# sdr_boosterpack.net
KiCad netlist of a schematic drawn in EAGLE
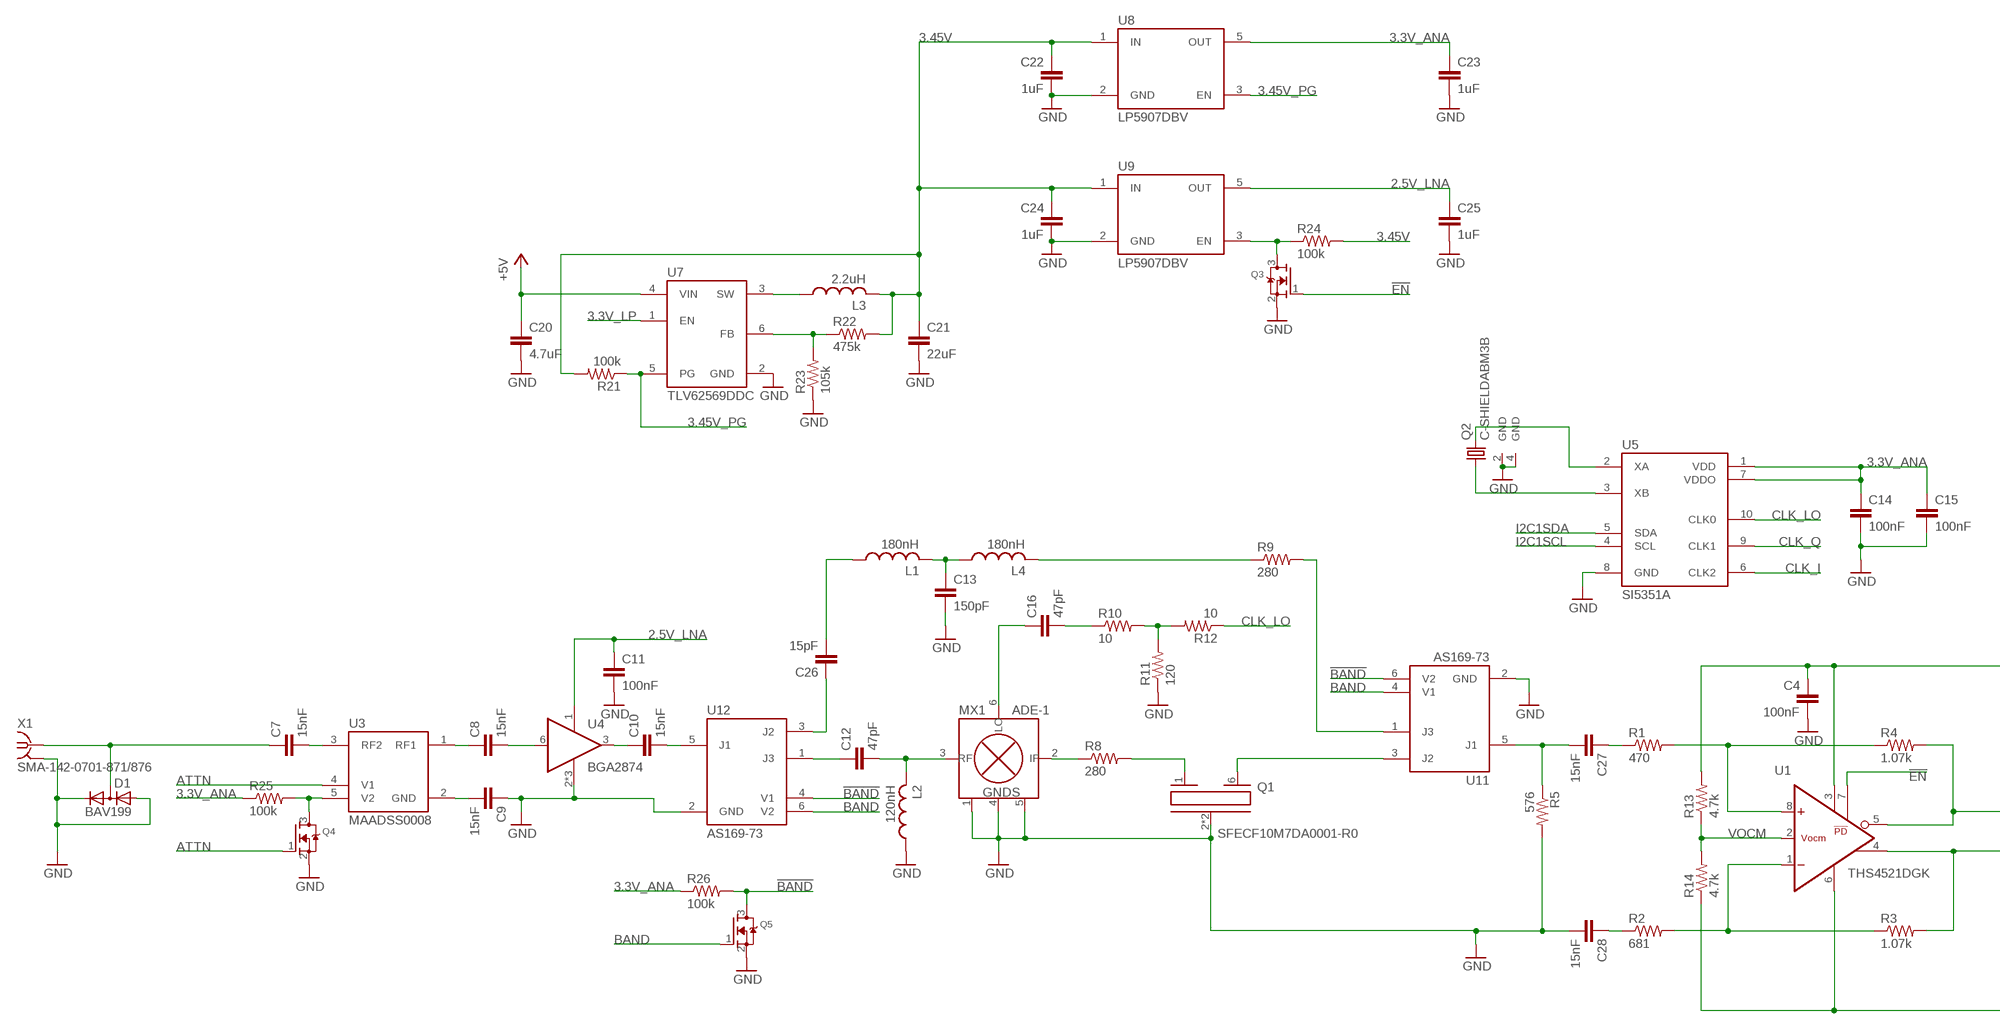
[diagram p0: schematic, sheet 1, part 1 of 2]
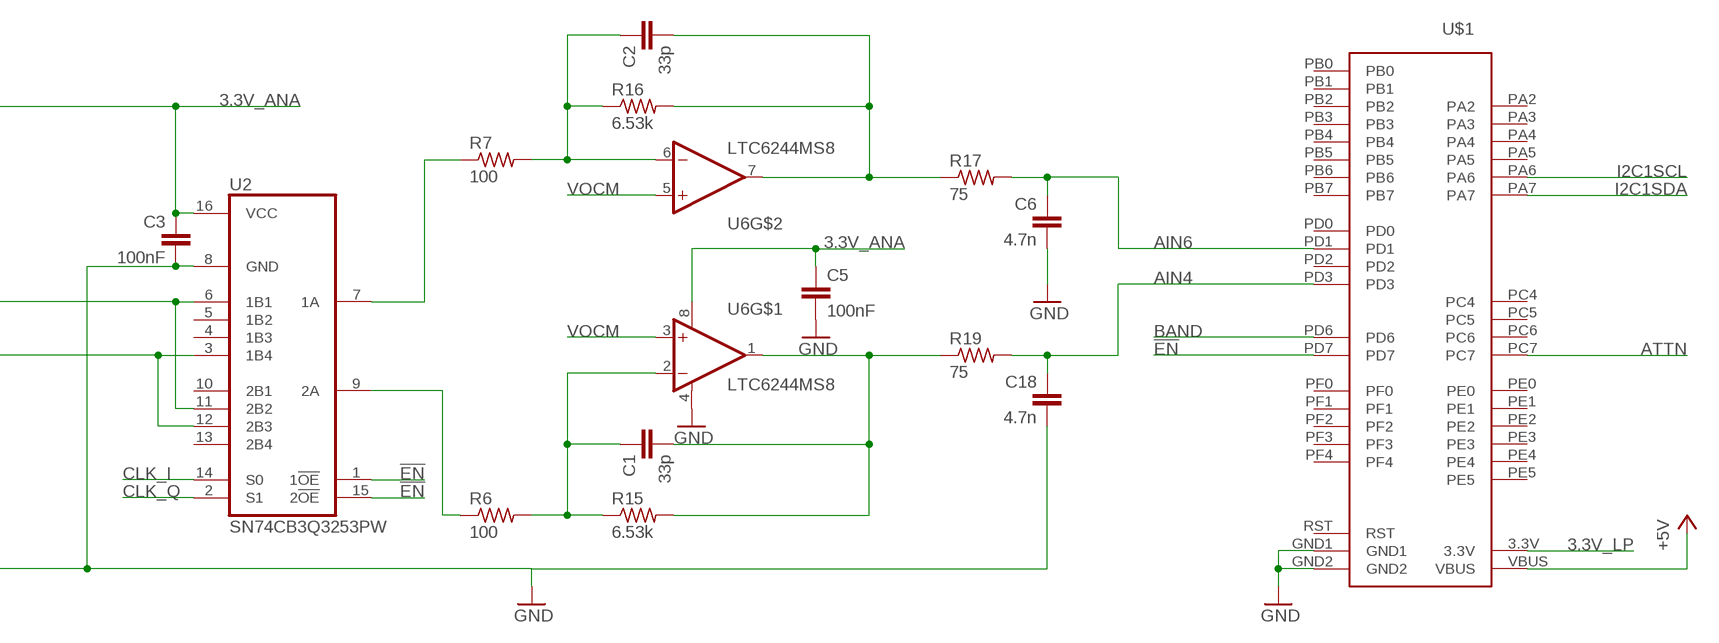
[diagram p1: schematic, sheet 1, part 2 of 2]

(export (version "E")
  (design (tool "Eeschema 10.0.6"))
  (components
    (comp (ref "C1")
      (value "33p")
      (footprint "eagle-import:C0603")
      (libsource (lib "eagle-import") (part "C-EUC0603"))
    )
    (comp (ref "C2")
      (value "33p")
      (footprint "eagle-import:C0603")
      (libsource (lib "eagle-import") (part "C-EUC0603"))
    )
    (comp (ref "C3")
      (value "100nF")
      (footprint "eagle-import:C0603")
      (libsource (lib "eagle-import") (part "C-EUC0603"))
    )
    (comp (ref "C4")
      (value "100nF")
      (footprint "eagle-import:C0603")
      (libsource (lib "eagle-import") (part "C-EUC0603"))
    )
    (comp (ref "C5")
      (value "100nF")
      (footprint "eagle-import:C0603")
      (libsource (lib "eagle-import") (part "C-EUC0603"))
    )
    (comp (ref "C6")
      (value "4.7n")
      (footprint "eagle-import:C0603")
      (libsource (lib "eagle-import") (part "C-EUC0603"))
    )
    (comp (ref "C7")
      (value "15nF")
      (footprint "eagle-import:C0603")
      (libsource (lib "eagle-import") (part "C-EUC0603"))
    )
    (comp (ref "C8")
      (value "15nF")
      (footprint "eagle-import:C0603")
      (libsource (lib "eagle-import") (part "C-EUC0603"))
    )
    (comp (ref "C9")
      (value "15nF")
      (footprint "eagle-import:C0603")
      (libsource (lib "eagle-import") (part "C-EUC0603"))
    )
    (comp (ref "C10")
      (value "15nF")
      (footprint "eagle-import:C0603")
      (libsource (lib "eagle-import") (part "C-EUC0603"))
    )
    (comp (ref "C11")
      (value "100nF")
      (footprint "eagle-import:C0603")
      (libsource (lib "eagle-import") (part "C-EUC0603"))
    )
    (comp (ref "C12")
      (value "47pF")
      (footprint "eagle-import:C0603")
      (libsource (lib "eagle-import") (part "C-EUC0603"))
    )
    (comp (ref "C13")
      (value "150pF")
      (footprint "eagle-import:C0603")
      (libsource (lib "eagle-import") (part "C-EUC0603"))
    )
    (comp (ref "C14")
      (value "100nF")
      (footprint "eagle-import:C0603")
      (libsource (lib "eagle-import") (part "C-EUC0603"))
    )
    (comp (ref "C15")
      (value "100nF")
      (footprint "eagle-import:C0603")
      (libsource (lib "eagle-import") (part "C-EUC0603"))
    )
    (comp (ref "C16")
      (value "47pF")
      (footprint "eagle-import:C0603")
      (libsource (lib "eagle-import") (part "C-EUC0603"))
    )
    (comp (ref "C18")
      (value "4.7n")
      (footprint "eagle-import:C0603")
      (libsource (lib "eagle-import") (part "C-EUC0603"))
    )
    (comp (ref "C20")
      (value "4.7uF")
      (footprint "eagle-import:C0805")
      (libsource (lib "eagle-import") (part "C-EUC0805"))
    )
    (comp (ref "C21")
      (value "22uF")
      (footprint "eagle-import:C0805")
      (libsource (lib "eagle-import") (part "C-EUC0805"))
    )
    (comp (ref "C22")
      (value "1uF")
      (footprint "eagle-import:C0805")
      (libsource (lib "eagle-import") (part "C-EUC0805"))
    )
    (comp (ref "C23")
      (value "1uF")
      (footprint "eagle-import:C0805")
      (libsource (lib "eagle-import") (part "C-EUC0805"))
    )
    (comp (ref "C24")
      (value "1uF")
      (footprint "eagle-import:C0805")
      (libsource (lib "eagle-import") (part "C-EUC0805"))
    )
    (comp (ref "C25")
      (value "1uF")
      (footprint "eagle-import:C0805")
      (libsource (lib "eagle-import") (part "C-EUC0805"))
    )
    (comp (ref "C26")
      (value "15pF")
      (footprint "eagle-import:C0603")
      (libsource (lib "eagle-import") (part "C-EUC0603"))
    )
    (comp (ref "C27")
      (value "15nF")
      (footprint "eagle-import:C0603")
      (libsource (lib "eagle-import") (part "C-EUC0603"))
    )
    (comp (ref "C28")
      (value "15nF")
      (footprint "eagle-import:C0603")
      (libsource (lib "eagle-import") (part "C-EUC0603"))
    )
    (comp (ref "D1")
      (value "BAV199")
      (footprint "eagle-import:SOT23")
      (libsource (lib "eagle-import") (part "BAV199"))
    )
    (comp (ref "L1")
      (value "180nH")
      (footprint "eagle-import:C0603")
      (libsource (lib "eagle-import") (part "L-US0603CS"))
    )
    (comp (ref "L2")
      (value "120nH")
      (footprint "eagle-import:C0603")
      (libsource (lib "eagle-import") (part "L-US0603CS"))
    )
    (comp (ref "L3")
      (value "2.2uH")
      (footprint "eagle-import:XAL4040")
      (libsource (lib "eagle-import") (part "L-USXAL4040"))
    )
    (comp (ref "L4")
      (value "180nH")
      (footprint "eagle-import:C0603")
      (libsource (lib "eagle-import") (part "L-US0603CS"))
    )
    (comp (ref "MX1")
      (value "ADE-1")
      (footprint "eagle-import:CD636")
      (libsource (lib "eagle-import") (part "ADE-1"))
    )
    (comp (ref "Q1")
      (value "SFECF10M7DA0001-R0")
      (footprint "eagle-import:SFECF")
      (libsource (lib "eagle-import") (part "SFECF"))
    )
    (comp (ref "Q2")
      (value "C-SHIELDABM3B")
      (footprint "eagle-import:ABM3B")
      (libsource (lib "eagle-import") (part "C-SHIELDABM3B"))
    )
    (comp (ref "Q3")
      (value "MOSFET-NREFLOW")
      (footprint "eagle-import:SOT23")
      (libsource (lib "eagle-import") (part "MOSFET-NREFLOW"))
    )
    (comp (ref "Q4")
      (value "MOSFET-NREFLOW")
      (footprint "eagle-import:SOT23")
      (libsource (lib "eagle-import") (part "MOSFET-NREFLOW"))
    )
    (comp (ref "Q5")
      (value "MOSFET-NREFLOW")
      (footprint "eagle-import:SOT23")
      (libsource (lib "eagle-import") (part "MOSFET-NREFLOW"))
    )
    (comp (ref "R1")
      (value "470")
      (footprint "eagle-import:R0603")
      (libsource (lib "eagle-import") (part "R-US_R0603"))
    )
    (comp (ref "R2")
      (value "681")
      (footprint "eagle-import:R0603")
      (libsource (lib "eagle-import") (part "R-US_R0603"))
    )
    (comp (ref "R3")
      (value "1.07k")
      (footprint "eagle-import:R0603")
      (libsource (lib "eagle-import") (part "R-US_R0603"))
    )
    (comp (ref "R4")
      (value "1.07k")
      (footprint "eagle-import:R0603")
      (libsource (lib "eagle-import") (part "R-US_R0603"))
    )
    (comp (ref "R5")
      (value "576")
      (footprint "eagle-import:R0603")
      (libsource (lib "eagle-import") (part "R-US_R0603"))
    )
    (comp (ref "R6")
      (value "100")
      (footprint "eagle-import:R0603")
      (libsource (lib "eagle-import") (part "R-US_R0603"))
    )
    (comp (ref "R7")
      (value "100")
      (footprint "eagle-import:R0603")
      (libsource (lib "eagle-import") (part "R-US_R0603"))
    )
    (comp (ref "R8")
      (value "280")
      (footprint "eagle-import:R0603")
      (libsource (lib "eagle-import") (part "R-US_R0603"))
    )
    (comp (ref "R9")
      (value "280")
      (footprint "eagle-import:R0603")
      (libsource (lib "eagle-import") (part "R-US_R0603"))
    )
    (comp (ref "R10")
      (value "10")
      (footprint "eagle-import:R0603")
      (libsource (lib "eagle-import") (part "R-US_R0603"))
    )
    (comp (ref "R11")
      (value "120")
      (footprint "eagle-import:R0603")
      (libsource (lib "eagle-import") (part "R-US_R0603"))
    )
    (comp (ref "R12")
      (value "10")
      (footprint "eagle-import:R0603")
      (libsource (lib "eagle-import") (part "R-US_R0603"))
    )
    (comp (ref "R13")
      (value "4.7k")
      (footprint "eagle-import:R0603")
      (libsource (lib "eagle-import") (part "R-US_R0603"))
    )
    (comp (ref "R14")
      (value "4.7k")
      (footprint "eagle-import:R0603")
      (libsource (lib "eagle-import") (part "R-US_R0603"))
    )
    (comp (ref "R15")
      (value "6.53k")
      (footprint "eagle-import:R0603")
      (libsource (lib "eagle-import") (part "R-US_R0603"))
    )
    (comp (ref "R16")
      (value "6.53k")
      (footprint "eagle-import:R0603")
      (libsource (lib "eagle-import") (part "R-US_R0603"))
    )
    (comp (ref "R17")
      (value "75")
      (footprint "eagle-import:R0603")
      (libsource (lib "eagle-import") (part "R-US_R0603"))
    )
    (comp (ref "R19")
      (value "75")
      (footprint "eagle-import:R0603")
      (libsource (lib "eagle-import") (part "R-US_R0603"))
    )
    (comp (ref "R21")
      (value "100k")
      (footprint "eagle-import:R0603")
      (libsource (lib "eagle-import") (part "R-US_R0603"))
    )
    (comp (ref "R22")
      (value "475k")
      (footprint "eagle-import:R0603")
      (libsource (lib "eagle-import") (part "R-US_R0603"))
    )
    (comp (ref "R23")
      (value "105k")
      (footprint "eagle-import:R0603")
      (libsource (lib "eagle-import") (part "R-US_R0603"))
    )
    (comp (ref "R24")
      (value "100k")
      (footprint "eagle-import:R0603")
      (libsource (lib "eagle-import") (part "R-US_R0603"))
    )
    (comp (ref "R25")
      (value "100k")
      (footprint "eagle-import:R0603")
      (libsource (lib "eagle-import") (part "R-US_R0603"))
    )
    (comp (ref "R26")
      (value "100k")
      (footprint "eagle-import:R0603")
      (libsource (lib "eagle-import") (part "R-US_R0603"))
    )
    (comp (ref "U$1")
      (value "STELLARIS-LAUNCHPADSTELLARIS-LAUNCHPAD-XL-HALF-LENGTH")
      (footprint "eagle-import:LAUNCHPAD-XL-HALF-LENGTH")
      (libsource (lib "eagle-import") (part "STELLARIS-LAUNCHPADSTELLARIS-LAUNCHPAD-XL-HALF-LENGTH"))
    )
    (comp (ref "U1")
      (value "THS4521DGK")
      (footprint "eagle-import:DGK_S-PDSO-G8")
      (libsource (lib "eagle-import") (part "THS4521DGK"))
    )
    (comp (ref "U2")
      (value "SN74CB3Q3253PW")
      (footprint "eagle-import:PW_R-PDSO-G16")
      (libsource (lib "eagle-import") (part "SN74CB3Q3253PW"))
    )
    (comp (ref "U3")
      (value "MAADSS0008")
      (footprint "eagle-import:SOT23-5L")
      (libsource (lib "eagle-import") (part "MAADSS0008"))
    )
    (comp (ref "U4")
      (value "BGA2874")
      (footprint "eagle-import:SOT363_PHILIPS")
      (libsource (lib "eagle-import") (part "BGA2874"))
    )
    (comp (ref "U5")
      (value "SI5351A")
      (footprint "eagle-import:MSOP10")
      (libsource (lib "eagle-import") (part "SI5351A"))
    )
    (comp (ref "U6")
      (value "LTC6244MS8")
      (footprint "eagle-import:MSOP8")
      (libsource (lib "eagle-import") (part "LTC6244MS8"))
    )
    (comp (ref "U7")
      (value "TLV62569DDC")
      (footprint "eagle-import:SOT23-6")
      (libsource (lib "eagle-import") (part "TLV62569DDC"))
    )
    (comp (ref "U8")
      (value "LP5907DBV")
      (footprint "eagle-import:MF05A-M")
      (libsource (lib "eagle-import") (part "LP5907DBV"))
    )
    (comp (ref "U9")
      (value "LP5907DBV")
      (footprint "eagle-import:MF05A-M")
      (libsource (lib "eagle-import") (part "LP5907DBV"))
    )
    (comp (ref "U11")
      (value "AS169-73")
      (footprint "eagle-import:SOT23-6")
      (libsource (lib "eagle-import") (part "AS169-73"))
    )
    (comp (ref "U12")
      (value "AS169-73")
      (footprint "eagle-import:SOT23-6")
      (libsource (lib "eagle-import") (part "AS169-73"))
    )
    (comp (ref "X1")
      (value "SMA-142-0701-871/876")
      (footprint "eagle-import:J502-ND-142-0701-871_876")
      (fields (field (name "MF") "JOHNSON COMPONENTS") (field (name "MPN") "142-0701-871"))
      (libsource (lib "eagle-import") (part "SMA-142-0701-871/876"))
    )
  )
  (nets
    (net (code "1") (name "+5V") (class "Default")
      (node (ref "C20") (pin "1") (pinfunction "1_1") (pintype "passive"))
      (node (ref "U$1") (pin "VBUS") (pinfunction "VBUS_VBUS") (pintype "power_in"))
      (node (ref "U7") (pin "4") (pinfunction "VIN_4") (pintype "bidirectional"))
    )
    (net (code "2") (name "/2.5V_LNA") (class "Default")
      (node (ref "C11") (pin "1") (pinfunction "1_1") (pintype "passive"))
      (node (ref "C25") (pin "1") (pinfunction "1_1") (pintype "passive"))
      (node (ref "U4") (pin "1") (pinfunction "V+_1") (pintype "power_in"))
      (node (ref "U9") (pin "5") (pinfunction "OUT_5") (pintype "bidirectional"))
    )
    (net (code "3") (name "/3.3V_ANA") (class "Default")
      (node (ref "C14") (pin "1") (pinfunction "1_1") (pintype "passive"))
      (node (ref "C15") (pin "1") (pinfunction "1_1") (pintype "passive"))
      (node (ref "C23") (pin "1") (pinfunction "1_1") (pintype "passive"))
      (node (ref "C3") (pin "1") (pinfunction "1_1") (pintype "passive"))
      (node (ref "C4") (pin "1") (pinfunction "1_1") (pintype "passive"))
      (node (ref "C5") (pin "1") (pinfunction "1_1") (pintype "passive"))
      (node (ref "R13") (pin "2") (pinfunction "2_2") (pintype "passive"))
      (node (ref "R25") (pin "1") (pinfunction "1_1") (pintype "passive"))
      (node (ref "R26") (pin "1") (pinfunction "1_1") (pintype "passive"))
      (node (ref "U1") (pin "3") (pinfunction "V+_3") (pintype "power_in"))
      (node (ref "U2") (pin "16") (pinfunction "VCC_16") (pintype "bidirectional"))
      (node (ref "U5") (pin "1") (pinfunction "VDD_1") (pintype "bidirectional"))
      (node (ref "U5") (pin "7") (pinfunction "VDDO_7") (pintype "bidirectional"))
      (node (ref "U6") (pin "8") (pinfunction "V+_8") (pintype "power_in"))
      (node (ref "U8") (pin "5") (pinfunction "OUT_5") (pintype "bidirectional"))
    )
    (net (code "4") (name "/3.3V_LP") (class "Default")
      (node (ref "U$1") (pin "3.3V") (pinfunction "3.3V_3.3V") (pintype "power_in"))
      (node (ref "U7") (pin "1") (pinfunction "EN_1") (pintype "bidirectional"))
    )
    (net (code "5") (name "/3.45V") (class "Default")
      (node (ref "C21") (pin "1") (pinfunction "1_1") (pintype "passive"))
      (node (ref "C22") (pin "1") (pinfunction "1_1") (pintype "passive"))
      (node (ref "C24") (pin "1") (pinfunction "1_1") (pintype "passive"))
      (node (ref "L3") (pin "2") (pinfunction "2_2") (pintype "passive"))
      (node (ref "R21") (pin "2") (pinfunction "2_2") (pintype "passive"))
      (node (ref "R22") (pin "2") (pinfunction "2_2") (pintype "passive"))
      (node (ref "R24") (pin "2") (pinfunction "2_2") (pintype "passive"))
      (node (ref "U8") (pin "1") (pinfunction "IN_1") (pintype "bidirectional"))
      (node (ref "U9") (pin "1") (pinfunction "IN_1") (pintype "bidirectional"))
    )
    (net (code "6") (name "/3.45V_PG") (class "Default")
      (node (ref "R21") (pin "1") (pinfunction "1_1") (pintype "passive"))
      (node (ref "U7") (pin "5") (pinfunction "PG_5") (pintype "bidirectional"))
      (node (ref "U8") (pin "3") (pinfunction "EN_3") (pintype "bidirectional"))
    )
    (net (code "7") (name "/AIN4") (class "Default")
      (node (ref "C18") (pin "1") (pinfunction "1_1") (pintype "passive"))
      (node (ref "R19") (pin "2") (pinfunction "2_2") (pintype "passive"))
      (node (ref "U$1") (pin "PD3") (pinfunction "PD3_PD3") (pintype "bidirectional"))
    )
    (net (code "8") (name "/AIN6") (class "Default")
      (node (ref "C6") (pin "1") (pinfunction "1_1") (pintype "passive"))
      (node (ref "R17") (pin "2") (pinfunction "2_2") (pintype "passive"))
      (node (ref "U$1") (pin "PD1") (pinfunction "PD1_PD1") (pintype "bidirectional"))
    )
    (net (code "9") (name "/ATTN") (class "Default")
      (node (ref "Q4") (pin "1") (pinfunction "G_1") (pintype "bidirectional"))
      (node (ref "U$1") (pin "PC7") (pinfunction "PC7_PC7") (pintype "bidirectional"))
      (node (ref "U3") (pin "4") (pinfunction "V1_4") (pintype "bidirectional"))
    )
    (net (code "10") (name "/BAND") (class "Default")
      (node (ref "Q5") (pin "1") (pinfunction "G_1") (pintype "bidirectional"))
      (node (ref "U$1") (pin "PD6") (pinfunction "PD6_PD6") (pintype "bidirectional"))
      (node (ref "U11") (pin "4") (pinfunction "V1_4") (pintype "bidirectional"))
      (node (ref "U12") (pin "6") (pinfunction "V2_6") (pintype "bidirectional"))
    )
    (net (code "11") (name "/CLK_I") (class "Default")
      (node (ref "U2") (pin "14") (pinfunction "S0_14") (pintype "input"))
      (node (ref "U5") (pin "6") (pinfunction "CLK2_6") (pintype "bidirectional"))
    )
    (net (code "12") (name "/CLK_LO") (class "Default")
      (node (ref "R12") (pin "1") (pinfunction "1_1") (pintype "passive"))
      (node (ref "U5") (pin "10") (pinfunction "CLK0_10") (pintype "bidirectional"))
    )
    (net (code "13") (name "/CLK_Q") (class "Default")
      (node (ref "U2") (pin "2") (pinfunction "S1_2") (pintype "input"))
      (node (ref "U5") (pin "9") (pinfunction "CLK1_9") (pintype "bidirectional"))
    )
    (net (code "14") (name "/I2C1SCL") (class "Default")
      (node (ref "U$1") (pin "PA6") (pinfunction "PA6_PA6") (pintype "bidirectional"))
      (node (ref "U5") (pin "4") (pinfunction "SCL_4") (pintype "bidirectional"))
    )
    (net (code "15") (name "/I2C1SDA") (class "Default")
      (node (ref "U$1") (pin "PA7") (pinfunction "PA7_PA7") (pintype "bidirectional"))
      (node (ref "U5") (pin "5") (pinfunction "SDA_5") (pintype "bidirectional"))
    )
    (net (code "16") (name "/RST") (class "Default")
      (node (ref "U$1") (pin "RST") (pinfunction "RST_RST") (pintype "power_in"))
    )
    (net (code "17") (name "/VOCM") (class "Default")
      (node (ref "R13") (pin "1") (pinfunction "1_1") (pintype "passive"))
      (node (ref "R14") (pin "2") (pinfunction "2_2") (pintype "passive"))
      (node (ref "U1") (pin "2") (pinfunction "VOCM_2") (pintype "input"))
      (node (ref "U6") (pin "3") (pinfunction "+IN_3") (pintype "input"))
      (node (ref "U6") (pin "5") (pinfunction "+IN_5") (pintype "input"))
    )
    (net (code "18") (name "/~{BAND}") (class "Default")
      (node (ref "Q5") (pin "3") (pinfunction "D_3") (pintype "bidirectional"))
      (node (ref "R26") (pin "2") (pinfunction "2_2") (pintype "passive"))
      (node (ref "U11") (pin "6") (pinfunction "V2_6") (pintype "bidirectional"))
      (node (ref "U12") (pin "4") (pinfunction "V1_4") (pintype "bidirectional"))
    )
    (net (code "19") (name "/~{EN}") (class "Default")
      (node (ref "Q3") (pin "1") (pinfunction "G_1") (pintype "bidirectional"))
      (node (ref "U$1") (pin "PD7") (pinfunction "PD7_PD7") (pintype "bidirectional"))
      (node (ref "U1") (pin "7") (pinfunction "PD_7") (pintype "input"))
      (node (ref "U2") (pin "1") (pinfunction "1~{OE}_1") (pintype "input"))
      (node (ref "U2") (pin "15") (pinfunction "2~{OE}_15") (pintype "input"))
    )
    (net (code "20") (name "GND") (class "Default")
      (node (ref "C11") (pin "2") (pinfunction "2_2") (pintype "passive"))
      (node (ref "C13") (pin "2") (pinfunction "2_2") (pintype "passive"))
      (node (ref "C14") (pin "2") (pinfunction "2_2") (pintype "passive"))
      (node (ref "C15") (pin "2") (pinfunction "2_2") (pintype "passive"))
      (node (ref "C18") (pin "2") (pinfunction "2_2") (pintype "passive"))
      (node (ref "C20") (pin "2") (pinfunction "2_2") (pintype "passive"))
      (node (ref "C21") (pin "2") (pinfunction "2_2") (pintype "passive"))
      (node (ref "C22") (pin "2") (pinfunction "2_2") (pintype "passive"))
      (node (ref "C23") (pin "2") (pinfunction "2_2") (pintype "passive"))
      (node (ref "C24") (pin "2") (pinfunction "2_2") (pintype "passive"))
      (node (ref "C25") (pin "2") (pinfunction "2_2") (pintype "passive"))
      (node (ref "C28") (pin "2") (pinfunction "2_2") (pintype "passive"))
      (node (ref "C3") (pin "2") (pinfunction "2_2") (pintype "passive"))
      (node (ref "C4") (pin "2") (pinfunction "2_2") (pintype "passive"))
      (node (ref "C5") (pin "2") (pinfunction "2_2") (pintype "passive"))
      (node (ref "C6") (pin "2") (pinfunction "2_2") (pintype "passive"))
      (node (ref "C9") (pin "1") (pinfunction "1_1") (pintype "passive"))
      (node (ref "D1") (pin "1") (pinfunction "A_1") (pintype "passive"))
      (node (ref "D1") (pin "2") (pinfunction "C_2") (pintype "passive"))
      (node (ref "L2") (pin "1") (pinfunction "1_1") (pintype "passive"))
      (node (ref "MX1") (pin "1") (pinfunction "GND_1") (pintype "passive"))
      (node (ref "MX1") (pin "4") (pinfunction "GND_4") (pintype "passive"))
      (node (ref "MX1") (pin "5") (pinfunction "GND_5") (pintype "passive"))
      (node (ref "Q1") (pin "2") (pinfunction "GND_2") (pintype "bidirectional"))
      (node (ref "Q1") (pin "5") (pinfunction "GND_5") (pintype "bidirectional"))
      (node (ref "Q2") (pin "2") (pinfunction "GND_2") (pintype "bidirectional"))
      (node (ref "Q2") (pin "4") (pinfunction "GND_4") (pintype "bidirectional"))
      (node (ref "Q3") (pin "2") (pinfunction "S_2") (pintype "bidirectional"))
      (node (ref "Q4") (pin "2") (pinfunction "S_2") (pintype "bidirectional"))
      (node (ref "Q5") (pin "2") (pinfunction "S_2") (pintype "bidirectional"))
      (node (ref "R11") (pin "1") (pinfunction "1_1") (pintype "passive"))
      (node (ref "R14") (pin "1") (pinfunction "1_1") (pintype "passive"))
      (node (ref "R23") (pin "1") (pinfunction "1_1") (pintype "passive"))
      (node (ref "R5") (pin "2") (pinfunction "2_2") (pintype "passive"))
      (node (ref "U$1") (pin "GND1") (pinfunction "GND1_GND1") (pintype "bidirectional"))
      (node (ref "U$1") (pin "GND2") (pinfunction "GND2_GND2") (pintype "power_in"))
      (node (ref "U1") (pin "6") (pinfunction "V-_6") (pintype "power_in"))
      (node (ref "U11") (pin "2") (pinfunction "GND_2") (pintype "bidirectional"))
      (node (ref "U12") (pin "2") (pinfunction "GND_2") (pintype "bidirectional"))
      (node (ref "U2") (pin "8") (pinfunction "GND_8") (pintype "bidirectional"))
      (node (ref "U4") (pin "2") (pinfunction "V-_2") (pintype "power_in"))
      (node (ref "U4") (pin "4") (pinfunction "V-_4") (pintype "power_in"))
      (node (ref "U4") (pin "5") (pinfunction "V-_5") (pintype "power_in"))
      (node (ref "U5") (pin "8") (pinfunction "GND_8") (pintype "bidirectional"))
      (node (ref "U6") (pin "4") (pinfunction "V-_4") (pintype "power_in"))
      (node (ref "U7") (pin "2") (pinfunction "GND_2") (pintype "bidirectional"))
      (node (ref "U8") (pin "2") (pinfunction "GND_2") (pintype "bidirectional"))
      (node (ref "U9") (pin "2") (pinfunction "GND_2") (pintype "bidirectional"))
      (node (ref "X1") (pin "G@1") (pinfunction "2_G@1") (pintype "passive"))
      (node (ref "X1") (pin "G@2") (pinfunction "2_G@2") (pintype "passive"))
      (node (ref "X1") (pin "G@3") (pinfunction "2_G@3") (pintype "passive"))
      (node (ref "X1") (pin "G@4") (pinfunction "2_G@4") (pintype "passive"))
    )
    (net (code "21") (name "Net-(C13-Pad1)") (class "Default")
      (node (ref "C13") (pin "1") (pinfunction "1_1") (pintype "passive"))
      (node (ref "L1") (pin "2") (pinfunction "2_2") (pintype "passive"))
      (node (ref "L4") (pin "1") (pinfunction "1_1") (pintype "passive"))
    )
    (net (code "22") (name "Net-(C16-Pad2)") (class "Default")
      (node (ref "C16") (pin "2") (pinfunction "2_2") (pintype "passive"))
      (node (ref "R10") (pin "1") (pinfunction "1_1") (pintype "passive"))
    )
    (net (code "23") (name "Net-(C26-Pad2)") (class "Default")
      (node (ref "C26") (pin "2") (pinfunction "2_2") (pintype "passive"))
      (node (ref "L1") (pin "1") (pinfunction "1_1") (pintype "passive"))
    )
    (net (code "24") (name "Net-(C27-Pad1)") (class "Default")
      (node (ref "C27") (pin "1") (pinfunction "1_1") (pintype "passive"))
      (node (ref "R1") (pin "1") (pinfunction "1_1") (pintype "passive"))
    )
    (net (code "25") (name "Net-(C28-Pad1)") (class "Default")
      (node (ref "C28") (pin "1") (pinfunction "1_1") (pintype "passive"))
      (node (ref "R2") (pin "1") (pinfunction "1_1") (pintype "passive"))
    )
    (net (code "26") (name "Net-(D1-AC)") (class "Default")
      (node (ref "C7") (pin "1") (pinfunction "1_1") (pintype "passive"))
      (node (ref "D1") (pin "3") (pinfunction "AC_3") (pintype "passive"))
      (node (ref "X1") (pin "1") (pinfunction "1_1") (pintype "passive"))
    )
    (net (code "27") (name "Net-(L4-Pad2)") (class "Default")
      (node (ref "L4") (pin "2") (pinfunction "2_2") (pintype "passive"))
      (node (ref "R9") (pin "1") (pinfunction "1_1") (pintype "passive"))
    )
    (net (code "28") (name "Net-(MX1-IF)") (class "Default")
      (node (ref "MX1") (pin "2") (pinfunction "IF_2") (pintype "passive"))
      (node (ref "R8") (pin "1") (pinfunction "1_1") (pintype "passive"))
    )
    (net (code "29") (name "Net-(MX1-LO)") (class "Default")
      (node (ref "C16") (pin "1") (pinfunction "1_1") (pintype "passive"))
      (node (ref "MX1") (pin "6") (pinfunction "LO_6") (pintype "passive"))
    )
    (net (code "30") (name "Net-(MX1-RF)") (class "Default")
      (node (ref "C12") (pin "2") (pinfunction "2_2") (pintype "passive"))
      (node (ref "L2") (pin "2") (pinfunction "2_2") (pintype "passive"))
      (node (ref "MX1") (pin "3") (pinfunction "RF_3") (pintype "passive"))
    )
    (net (code "31") (name "Net-(Q1-IN)") (class "Default")
      (node (ref "Q1") (pin "1") (pinfunction "IN_1") (pintype "bidirectional"))
      (node (ref "R8") (pin "2") (pinfunction "2_2") (pintype "passive"))
    )
    (net (code "32") (name "Net-(Q1-OUT)") (class "Default")
      (node (ref "Q1") (pin "6") (pinfunction "OUT_6") (pintype "bidirectional"))
      (node (ref "U11") (pin "3") (pinfunction "J2_3") (pintype "bidirectional"))
    )
    (net (code "33") (name "Net-(Q2-2)") (class "Default")
      (node (ref "Q2") (pin "3") (pinfunction "2_3") (pintype "passive"))
      (node (ref "U5") (pin "2") (pinfunction "XA_2") (pintype "bidirectional"))
    )
    (net (code "34") (name "Net-(Q3-D)") (class "Default")
      (node (ref "Q3") (pin "3") (pinfunction "D_3") (pintype "bidirectional"))
      (node (ref "R24") (pin "1") (pinfunction "1_1") (pintype "passive"))
      (node (ref "U9") (pin "3") (pinfunction "EN_3") (pintype "bidirectional"))
    )
    (net (code "35") (name "Net-(Q4-D)") (class "Default")
      (node (ref "Q4") (pin "3") (pinfunction "D_3") (pintype "bidirectional"))
      (node (ref "R25") (pin "2") (pinfunction "2_2") (pintype "passive"))
      (node (ref "U3") (pin "5") (pinfunction "V2_5") (pintype "bidirectional"))
    )
    (net (code "36") (name "Net-(R10-Pad2)") (class "Default")
      (node (ref "R10") (pin "2") (pinfunction "2_2") (pintype "passive"))
      (node (ref "R11") (pin "2") (pinfunction "2_2") (pintype "passive"))
      (node (ref "R12") (pin "2") (pinfunction "2_2") (pintype "passive"))
    )
    (net (code "37") (name "Net-(U1-+IN)") (class "Default")
      (node (ref "R1") (pin "2") (pinfunction "2_2") (pintype "passive"))
      (node (ref "R4") (pin "1") (pinfunction "1_1") (pintype "passive"))
      (node (ref "U1") (pin "8") (pinfunction "+IN_8") (pintype "input"))
    )
    (net (code "38") (name "Net-(U1-+OUT)") (class "Default")
      (node (ref "R3") (pin "2") (pinfunction "2_2") (pintype "passive"))
      (node (ref "U1") (pin "4") (pinfunction "+OUT_4") (pintype "output"))
      (node (ref "U2") (pin "12") (pinfunction "2B3_12") (pintype "bidirectional"))
      (node (ref "U2") (pin "3") (pinfunction "1B4_3") (pintype "bidirectional"))
    )
    (net (code "39") (name "Net-(U1--IN)") (class "Default")
      (node (ref "R2") (pin "2") (pinfunction "2_2") (pintype "passive"))
      (node (ref "R3") (pin "1") (pinfunction "1_1") (pintype "passive"))
      (node (ref "U1") (pin "1") (pinfunction "-IN_1") (pintype "input"))
    )
    (net (code "40") (name "Net-(U1--OUT)") (class "Default")
      (node (ref "R4") (pin "2") (pinfunction "2_2") (pintype "passive"))
      (node (ref "U1") (pin "5") (pinfunction "-OUT_5") (pintype "output"))
      (node (ref "U2") (pin "11") (pinfunction "2B2_11") (pintype "bidirectional"))
      (node (ref "U2") (pin "6") (pinfunction "1B1_6") (pintype "bidirectional"))
    )
    (net (code "41") (name "Net-(U2-1A)") (class "Default")
      (node (ref "R7") (pin "1") (pinfunction "1_1") (pintype "passive"))
      (node (ref "U2") (pin "7") (pinfunction "1A_7") (pintype "bidirectional"))
    )
    (net (code "42") (name "Net-(U2-2A)") (class "Default")
      (node (ref "R6") (pin "1") (pinfunction "1_1") (pintype "passive"))
      (node (ref "U2") (pin "9") (pinfunction "2A_9") (pintype "bidirectional"))
    )
    (net (code "43") (name "Net-(U3-GND)") (class "Default")
      (node (ref "C9") (pin "2") (pinfunction "2_2") (pintype "passive"))
      (node (ref "U3") (pin "2") (pinfunction "GND_2") (pintype "bidirectional"))
    )
    (net (code "44") (name "Net-(U3-RF1)") (class "Default")
      (node (ref "C8") (pin "1") (pinfunction "1_1") (pintype "passive"))
      (node (ref "U3") (pin "1") (pinfunction "RF1_1") (pintype "bidirectional"))
    )
    (net (code "45") (name "Net-(U3-RF2)") (class "Default")
      (node (ref "C7") (pin "2") (pinfunction "2_2") (pintype "passive"))
      (node (ref "U3") (pin "3") (pinfunction "RF2_3") (pintype "bidirectional"))
    )
    (net (code "46") (name "Net-(U4--IN)") (class "Default")
      (node (ref "C8") (pin "2") (pinfunction "2_2") (pintype "passive"))
      (node (ref "U4") (pin "6") (pinfunction "-IN_6") (pintype "input"))
    )
    (net (code "47") (name "Net-(U4-OUT)") (class "Default")
      (node (ref "C10") (pin "1") (pinfunction "1_1") (pintype "passive"))
      (node (ref "U4") (pin "3") (pinfunction "OUT_3") (pintype "output"))
    )
    (net (code "48") (name "Net-(U5-XB)") (class "Default")
      (node (ref "Q2") (pin "1") (pinfunction "1_1") (pintype "passive"))
      (node (ref "U5") (pin "3") (pinfunction "XB_3") (pintype "bidirectional"))
    )
    (net (code "49") (name "Net-(U6A--IN)") (class "Default")
      (node (ref "C1") (pin "1") (pinfunction "1_1") (pintype "passive"))
      (node (ref "R15") (pin "1") (pinfunction "1_1") (pintype "passive"))
      (node (ref "R6") (pin "2") (pinfunction "2_2") (pintype "passive"))
      (node (ref "U6") (pin "2") (pinfunction "-IN_2") (pintype "input"))
    )
    (net (code "50") (name "Net-(U6A-OUT)") (class "Default")
      (node (ref "C1") (pin "2") (pinfunction "2_2") (pintype "passive"))
      (node (ref "R15") (pin "2") (pinfunction "2_2") (pintype "passive"))
      (node (ref "R19") (pin "1") (pinfunction "1_1") (pintype "passive"))
      (node (ref "U6") (pin "1") (pinfunction "OUT_1") (pintype "output"))
    )
    (net (code "51") (name "Net-(U6B--IN)") (class "Default")
      (node (ref "C2") (pin "1") (pinfunction "1_1") (pintype "passive"))
      (node (ref "R16") (pin "1") (pinfunction "1_1") (pintype "passive"))
      (node (ref "R7") (pin "2") (pinfunction "2_2") (pintype "passive"))
      (node (ref "U6") (pin "6") (pinfunction "-IN_6") (pintype "input"))
    )
    (net (code "52") (name "Net-(U6B-OUT)") (class "Default")
      (node (ref "C2") (pin "2") (pinfunction "2_2") (pintype "passive"))
      (node (ref "R16") (pin "2") (pinfunction "2_2") (pintype "passive"))
      (node (ref "R17") (pin "1") (pinfunction "1_1") (pintype "passive"))
      (node (ref "U6") (pin "7") (pinfunction "OUT_7") (pintype "output"))
    )
    (net (code "53") (name "Net-(U7-FB)") (class "Default")
      (node (ref "R22") (pin "1") (pinfunction "1_1") (pintype "passive"))
      (node (ref "R23") (pin "2") (pinfunction "2_2") (pintype "passive"))
      (node (ref "U7") (pin "6") (pinfunction "FB_6") (pintype "bidirectional"))
    )
    (net (code "54") (name "Net-(U7-SW)") (class "Default")
      (node (ref "L3") (pin "1") (pinfunction "1_1") (pintype "passive"))
      (node (ref "U7") (pin "3") (pinfunction "SW_3") (pintype "bidirectional"))
    )
    (net (code "55") (name "Net-(U11-J1)") (class "Default")
      (node (ref "C27") (pin "2") (pinfunction "2_2") (pintype "passive"))
      (node (ref "R5") (pin "1") (pinfunction "1_1") (pintype "passive"))
      (node (ref "U11") (pin "5") (pinfunction "J1_5") (pintype "bidirectional"))
    )
    (net (code "56") (name "Net-(U11-J3)") (class "Default")
      (node (ref "R9") (pin "2") (pinfunction "2_2") (pintype "passive"))
      (node (ref "U11") (pin "1") (pinfunction "J3_1") (pintype "bidirectional"))
    )
    (net (code "57") (name "Net-(U12-J1)") (class "Default")
      (node (ref "C10") (pin "2") (pinfunction "2_2") (pintype "passive"))
      (node (ref "U12") (pin "5") (pinfunction "J1_5") (pintype "bidirectional"))
    )
    (net (code "58") (name "Net-(U12-J2)") (class "Default")
      (node (ref "C26") (pin "1") (pinfunction "1_1") (pintype "passive"))
      (node (ref "U12") (pin "3") (pinfunction "J2_3") (pintype "bidirectional"))
    )
    (net (code "59") (name "Net-(U12-J3)") (class "Default")
      (node (ref "C12") (pin "1") (pinfunction "1_1") (pintype "passive"))
      (node (ref "U12") (pin "1") (pinfunction "J3_1") (pintype "bidirectional"))
    )
    (net (code "60") (name "unconnected-(U$1-PadPA2)") (class "Default")
      (node (ref "U$1") (pin "PA2") (pinfunction "PA2_PA2") (pintype "bidirectional"))
    )
    (net (code "61") (name "unconnected-(U$1-PadPA3)") (class "Default")
      (node (ref "U$1") (pin "PA3") (pinfunction "PA3_PA3") (pintype "bidirectional"))
    )
    (net (code "62") (name "unconnected-(U$1-PadPA4)") (class "Default")
      (node (ref "U$1") (pin "PA4") (pinfunction "PA4_PA4") (pintype "bidirectional"))
    )
    (net (code "63") (name "unconnected-(U$1-PadPA5)") (class "Default")
      (node (ref "U$1") (pin "PA5") (pinfunction "PA5_PA5") (pintype "bidirectional"))
    )
    (net (code "64") (name "unconnected-(U$1-PadPB0)") (class "Default")
      (node (ref "U$1") (pin "PB0") (pinfunction "PB0_PB0") (pintype "bidirectional"))
    )
    (net (code "65") (name "unconnected-(U$1-PadPB1)") (class "Default")
      (node (ref "U$1") (pin "PB1") (pinfunction "PB1_PB1") (pintype "bidirectional"))
    )
    (net (code "66") (name "unconnected-(U$1-PadPB2)") (class "Default")
      (node (ref "U$1") (pin "PB2") (pinfunction "PB2_PB2") (pintype "bidirectional"))
    )
    (net (code "67") (name "unconnected-(U$1-PadPB3)") (class "Default")
      (node (ref "U$1") (pin "PB3") (pinfunction "PB3_PB3") (pintype "bidirectional"))
    )
    (net (code "68") (name "unconnected-(U$1-PadPB4)") (class "Default")
      (node (ref "U$1") (pin "PB4") (pinfunction "PB4_PB4") (pintype "bidirectional"))
    )
    (net (code "69") (name "unconnected-(U$1-PadPB5)") (class "Default")
      (node (ref "U$1") (pin "PB5") (pinfunction "PB5_PB5") (pintype "bidirectional"))
    )
    (net (code "70") (name "unconnected-(U$1-PadPB6)") (class "Default")
      (node (ref "U$1") (pin "PB6") (pinfunction "PB6_PB6") (pintype "bidirectional"))
    )
    (net (code "71") (name "unconnected-(U$1-PadPB7)") (class "Default")
      (node (ref "U$1") (pin "PB7") (pinfunction "PB7_PB7") (pintype "bidirectional"))
    )
    (net (code "72") (name "unconnected-(U$1-PadPC4)") (class "Default")
      (node (ref "U$1") (pin "PC4") (pinfunction "PC4_PC4") (pintype "bidirectional"))
    )
    (net (code "73") (name "unconnected-(U$1-PadPC5)") (class "Default")
      (node (ref "U$1") (pin "PC5") (pinfunction "PC5_PC5") (pintype "bidirectional"))
    )
    (net (code "74") (name "unconnected-(U$1-PadPC6)") (class "Default")
      (node (ref "U$1") (pin "PC6") (pinfunction "PC6_PC6") (pintype "bidirectional"))
    )
    (net (code "75") (name "unconnected-(U$1-PadPD0)") (class "Default")
      (node (ref "U$1") (pin "PD0") (pinfunction "PD0_PD0") (pintype "bidirectional"))
    )
    (net (code "76") (name "unconnected-(U$1-PadPD2)") (class "Default")
      (node (ref "U$1") (pin "PD2") (pinfunction "PD2_PD2") (pintype "bidirectional"))
    )
    (net (code "77") (name "unconnected-(U$1-PadPE0)") (class "Default")
      (node (ref "U$1") (pin "PE0") (pinfunction "PE0_PE0") (pintype "bidirectional"))
    )
    (net (code "78") (name "unconnected-(U$1-PadPE1)") (class "Default")
      (node (ref "U$1") (pin "PE1") (pinfunction "PE1_PE1") (pintype "bidirectional"))
    )
    (net (code "79") (name "unconnected-(U$1-PadPE2)") (class "Default")
      (node (ref "U$1") (pin "PE2") (pinfunction "PE2_PE2") (pintype "bidirectional"))
    )
    (net (code "80") (name "unconnected-(U$1-PadPE3)") (class "Default")
      (node (ref "U$1") (pin "PE3") (pinfunction "PE3_PE3") (pintype "bidirectional"))
    )
    (net (code "81") (name "unconnected-(U$1-PadPE4)") (class "Default")
      (node (ref "U$1") (pin "PE4") (pinfunction "PE4_PE4") (pintype "bidirectional"))
    )
    (net (code "82") (name "unconnected-(U$1-PadPE5)") (class "Default")
      (node (ref "U$1") (pin "PE5") (pinfunction "PE5_PE5") (pintype "bidirectional"))
    )
    (net (code "83") (name "unconnected-(U$1-PadPF0)") (class "Default")
      (node (ref "U$1") (pin "PF0") (pinfunction "PF0_PF0") (pintype "bidirectional"))
    )
    (net (code "84") (name "unconnected-(U$1-PadPF1)") (class "Default")
      (node (ref "U$1") (pin "PF1") (pinfunction "PF1_PF1") (pintype "bidirectional"))
    )
    (net (code "85") (name "unconnected-(U$1-PadPF2)") (class "Default")
      (node (ref "U$1") (pin "PF2") (pinfunction "PF2_PF2") (pintype "bidirectional"))
    )
    (net (code "86") (name "unconnected-(U$1-PadPF3)") (class "Default")
      (node (ref "U$1") (pin "PF3") (pinfunction "PF3_PF3") (pintype "bidirectional"))
    )
    (net (code "87") (name "unconnected-(U$1-PadPF4)") (class "Default")
      (node (ref "U$1") (pin "PF4") (pinfunction "PF4_PF4") (pintype "bidirectional"))
    )
    (net (code "88") (name "unconnected-(U2-1B2-Pad5)") (class "Default")
      (node (ref "U2") (pin "5") (pinfunction "1B2_5") (pintype "bidirectional"))
    )
    (net (code "89") (name "unconnected-(U2-1B3-Pad4)") (class "Default")
      (node (ref "U2") (pin "4") (pinfunction "1B3_4") (pintype "bidirectional"))
    )
    (net (code "90") (name "unconnected-(U2-2B1-Pad10)") (class "Default")
      (node (ref "U2") (pin "10") (pinfunction "2B1_10") (pintype "bidirectional"))
    )
    (net (code "91") (name "unconnected-(U2-2B4-Pad13)") (class "Default")
      (node (ref "U2") (pin "13") (pinfunction "2B4_13") (pintype "bidirectional"))
    )
  )
)
